# badger.net
KiCad netlist of a schematic drawn in EAGLE
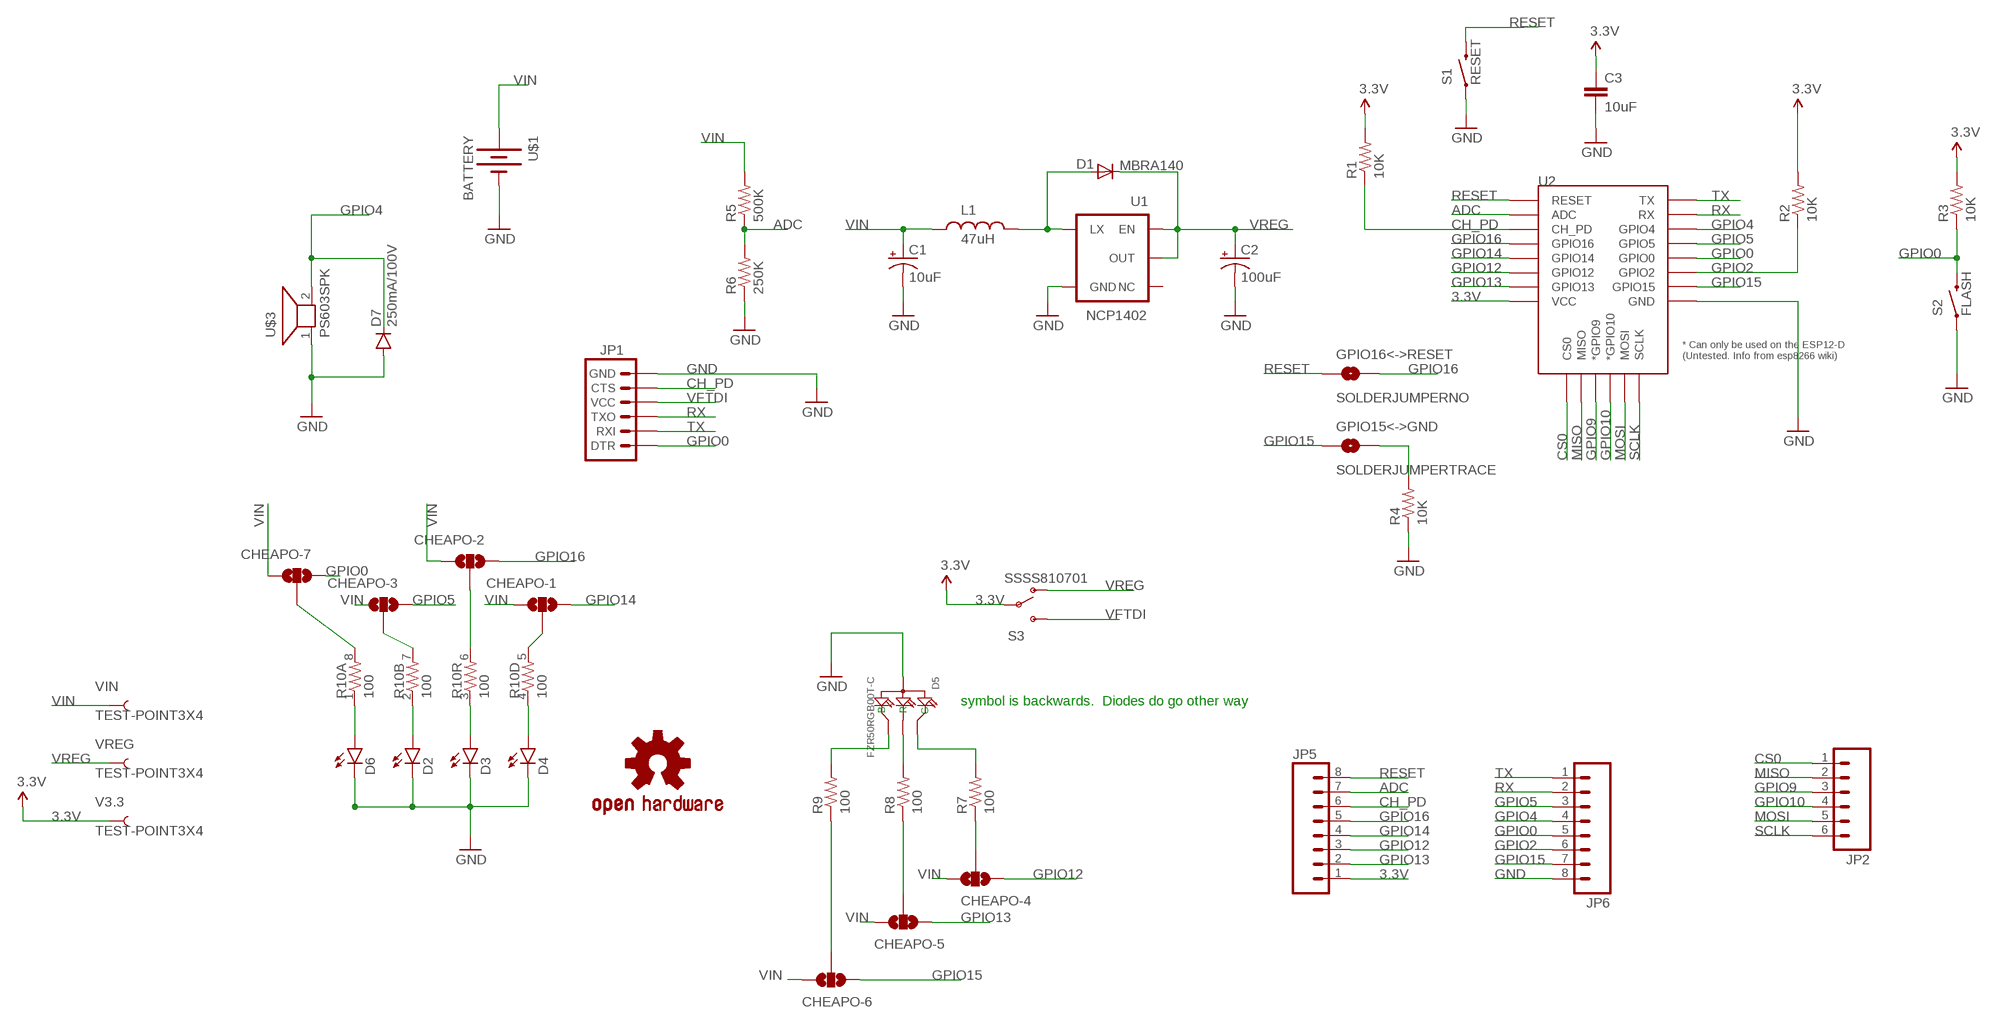
[diagram p0: schematic, sheet 1]

(export (version "E")
  (design (tool "Eeschema 10.0.6"))
  (components
    (comp (ref "C1")
      (value "10uF")
      (footprint "eagle-import:EIA3216")
      (libsource (lib "eagle-import") (part "CAP_POL1206"))
    )
    (comp (ref "C2")
      (value "100uF")
      (footprint "eagle-import:EIA3528")
      (libsource (lib "eagle-import") (part "CAP_POL3528"))
    )
    (comp (ref "C3")
      (value "10uF")
      (footprint "eagle-import:0603-CAP")
      (libsource (lib "eagle-import") (part "10UF-6.3V-20%(0603)"))
    )
    (comp (ref "CHEAPO-1")
      (value "SOLDERJUMPER_2WAYT")
      (footprint "eagle-import:SJ_2")
      (libsource (lib "eagle-import") (part "SOLDERJUMPER_2WAYT"))
    )
    (comp (ref "CHEAPO-2")
      (value "SOLDERJUMPER_2WAYT")
      (footprint "eagle-import:SJ_2")
      (libsource (lib "eagle-import") (part "SOLDERJUMPER_2WAYT"))
    )
    (comp (ref "CHEAPO-3")
      (value "SOLDERJUMPER_2WAYT")
      (footprint "eagle-import:SJ_2")
      (libsource (lib "eagle-import") (part "SOLDERJUMPER_2WAYT"))
    )
    (comp (ref "CHEAPO-4")
      (value "SOLDERJUMPER_2WAYT")
      (footprint "eagle-import:SJ_2")
      (libsource (lib "eagle-import") (part "SOLDERJUMPER_2WAYT"))
    )
    (comp (ref "CHEAPO-5")
      (value "SOLDERJUMPER_2WAYT")
      (footprint "eagle-import:SJ_2")
      (libsource (lib "eagle-import") (part "SOLDERJUMPER_2WAYT"))
    )
    (comp (ref "CHEAPO-6")
      (value "SOLDERJUMPER_2WAYT")
      (footprint "eagle-import:SJ_2")
      (libsource (lib "eagle-import") (part "SOLDERJUMPER_2WAYT"))
    )
    (comp (ref "CHEAPO-7")
      (value "SOLDERJUMPER_2WAYT")
      (footprint "eagle-import:SJ_2")
      (libsource (lib "eagle-import") (part "SOLDERJUMPER_2WAYT"))
    )
    (comp (ref "D1")
      (value "MBRA140")
      (footprint "eagle-import:SMA-DIODE")
      (libsource (lib "eagle-import") (part "DIODESMA"))
    )
    (comp (ref "D2")
      (value "LED-3MM-NO_SILK")
      (footprint "eagle-import:LED3MM-NS")
      (libsource (lib "eagle-import") (part "LED-3MM-NO_SILK"))
    )
    (comp (ref "D3")
      (value "LED-3MM-NO_SILK")
      (footprint "eagle-import:LED3MM-NS")
      (libsource (lib "eagle-import") (part "LED-3MM-NO_SILK"))
    )
    (comp (ref "D4")
      (value "LED-3MM-NO_SILK")
      (footprint "eagle-import:LED3MM-NS")
      (libsource (lib "eagle-import") (part "LED-3MM-NO_SILK"))
    )
    (comp (ref "D5")
      (value "FZR50RGB00T-C")
      (footprint "eagle-import:LED4-1.3-D5.0MM")
      (libsource (lib "eagle-import") (part "DIP-LED-RGB-COMMON-ANODE(4P-D5MM)"))
    )
    (comp (ref "D6")
      (value "LED-3MM-NO_SILK")
      (footprint "eagle-import:LED3MM-NS")
      (libsource (lib "eagle-import") (part "LED-3MM-NO_SILK"))
    )
    (comp (ref "D7")
      (value "250mA/100V")
      (footprint "eagle-import:SOD-323")
      (libsource (lib "eagle-import") (part "DIODEBAS16"))
    )
    (comp (ref "GPIO15<->GND")
      (value "SOLDERJUMPERTRACE")
      (footprint "eagle-import:SJ_2S-TRACE")
      (libsource (lib "eagle-import") (part "SOLDERJUMPERTRACE"))
    )
    (comp (ref "GPIO16<->RESET")
      (value "SOLDERJUMPERNO")
      (footprint "eagle-import:SJ_2S-NO")
      (libsource (lib "eagle-import") (part "SOLDERJUMPERNO"))
    )
    (comp (ref "JP1")
      (value "ARDUINO_SERIAL_PROGRAMLOCK")
      (footprint "eagle-import:1X06_LOCK")
      (libsource (lib "eagle-import") (part "ARDUINO_SERIAL_PROGRAMLOCK"))
    )
    (comp (ref "JP2")
      (value "M06LOCK")
      (footprint "eagle-import:1X06_LOCK")
      (libsource (lib "eagle-import") (part "M06LOCK"))
    )
    (comp (ref "JP5")
      (value "M08LOCK")
      (footprint "eagle-import:1X08_LOCK")
      (libsource (lib "eagle-import") (part "M08LOCK"))
    )
    (comp (ref "JP6")
      (value "M08LOCK")
      (footprint "eagle-import:1X08_LOCK")
      (libsource (lib "eagle-import") (part "M08LOCK"))
    )
    (comp (ref "L1")
      (value "47uH")
      (footprint "eagle-import:CR54")
      (libsource (lib "eagle-import") (part "INDUCTORCR54"))
    )
    (comp (ref "LOGO1")
      (value "OSHW-LOGOL-COPPER")
      (footprint "eagle-import:OSHW-LOGO-L_COPPER")
      (libsource (lib "eagle-import") (part "OSHW-LOGOL-COPPER"))
    )
    (comp (ref "R1")
      (value "10K")
      (footprint "eagle-import:0603-RES")
      (libsource (lib "eagle-import") (part "10KOHM-1/10W-1%(0603)0603"))
    )
    (comp (ref "R2")
      (value "10K")
      (footprint "eagle-import:0603-RES")
      (libsource (lib "eagle-import") (part "10KOHM-1/10W-1%(0603)0603"))
    )
    (comp (ref "R3")
      (value "10K")
      (footprint "eagle-import:0603-RES")
      (libsource (lib "eagle-import") (part "10KOHM-1/10W-1%(0603)0603"))
    )
    (comp (ref "R4")
      (value "10K")
      (footprint "eagle-import:0603-RES")
      (libsource (lib "eagle-import") (part "10KOHM-1/10W-1%(0603)0603"))
    )
    (comp (ref "R5")
      (value "500K")
      (footprint "eagle-import:0603-RES")
      (libsource (lib "eagle-import") (part "RESISTOR0603"))
    )
    (comp (ref "R6")
      (value "250K")
      (footprint "eagle-import:0603-RES")
      (libsource (lib "eagle-import") (part "RESISTOR0603"))
    )
    (comp (ref "R7")
      (value "100")
      (footprint "eagle-import:1206")
      (libsource (lib "eagle-import") (part "RESISTOR1206"))
    )
    (comp (ref "R8")
      (value "100")
      (footprint "eagle-import:1206")
      (libsource (lib "eagle-import") (part "RESISTOR1206"))
    )
    (comp (ref "R9")
      (value "100")
      (footprint "eagle-import:1206")
      (libsource (lib "eagle-import") (part "RESISTOR1206"))
    )
    (comp (ref "R10")
      (value "100")
      (footprint "eagle-import:0603-ARV")
      (libsource (lib "eagle-import") (part "RESISTOR-ARRAY0603-ARV"))
    )
    (comp (ref "S1")
      (value "RESET")
      (footprint "eagle-import:TACTILE-SWITCH-SMD")
      (libsource (lib "eagle-import") (part "SWITCH-MOMENTARY-2SMD"))
    )
    (comp (ref "S2")
      (value "FLASH")
      (footprint "eagle-import:TACTILE-SWITCH-SMD")
      (libsource (lib "eagle-import") (part "SWITCH-MOMENTARY-2SMD"))
    )
    (comp (ref "S3")
      (value "SSSS810701")
      (footprint "eagle-import:SSSS8")
      (libsource (lib "eagle-import") (part "SSSS810701"))
    )
    (comp (ref "U$1")
      (value "BATTERY")
      (footprint "eagle-import:HOLDER")
      (libsource (lib "eagle-import") (part "BATTERY"))
    )
    (comp (ref "U$3")
      (value "PS603SPK")
      (footprint "eagle-import:PS603")
      (libsource (lib "eagle-import") (part "PS603SPK"))
    )
    (comp (ref "U1")
      (value "NCP1402")
      (footprint "eagle-import:SOT23-5")
      (libsource (lib "eagle-import") (part "V_REG_NCP1400SOT23-5"))
    )
    (comp (ref "U2")
      (value "ESP12ESMD")
      (footprint "eagle-import:ESP12E-SMD")
      (libsource (lib "eagle-import") (part "ESP12ESMD"))
    )
    (comp (ref "V3.3")
      (value "TEST-POINT3X4")
      (footprint "eagle-import:PAD.03X.04")
      (libsource (lib "eagle-import") (part "TEST-POINT3X4"))
    )
    (comp (ref "VIN")
      (value "TEST-POINT3X4")
      (footprint "eagle-import:PAD.03X.04")
      (libsource (lib "eagle-import") (part "TEST-POINT3X4"))
    )
    (comp (ref "VREG")
      (value "TEST-POINT3X4")
      (footprint "eagle-import:PAD.03X.04")
      (libsource (lib "eagle-import") (part "TEST-POINT3X4"))
    )
  )
  (nets
    (net (code "1") (name "/ADC") (class "Default")
      (node (ref "JP5") (pin "7") (pinfunction "7_7") (pintype "passive"))
      (node (ref "R5") (pin "1") (pinfunction "1_1") (pintype "passive"))
      (node (ref "R6") (pin "2") (pinfunction "2_2") (pintype "passive"))
      (node (ref "U2") (pin "ADC") (pinfunction "ADC_ADC") (pintype "bidirectional"))
    )
    (net (code "2") (name "/CH_PD") (class "Default")
      (node (ref "JP1") (pin "5") (pinfunction "CTS_5") (pintype "passive"))
      (node (ref "JP5") (pin "6") (pinfunction "6_6") (pintype "passive"))
      (node (ref "R1") (pin "1") (pinfunction "1_1") (pintype "passive"))
      (node (ref "U2") (pin "CH_PD") (pinfunction "CH_PD_CH_PD") (pintype "bidirectional"))
    )
    (net (code "3") (name "/CS0") (class "Default")
      (node (ref "JP2") (pin "1") (pinfunction "1_1") (pintype "passive"))
      (node (ref "U2") (pin "CS0") (pinfunction "CS0_CS0") (pintype "bidirectional"))
    )
    (net (code "4") (name "/GPIO0") (class "Default")
      (node (ref "CHEAPO-7") (pin "3") (pinfunction "3_3") (pintype "passive"))
      (node (ref "JP1") (pin "1") (pinfunction "DTR_1") (pintype "passive"))
      (node (ref "JP6") (pin "5") (pinfunction "5_5") (pintype "passive"))
      (node (ref "R3") (pin "1") (pinfunction "1_1") (pintype "passive"))
      (node (ref "S2") (pin "3") (pinfunction "2_3") (pintype "passive"))
      (node (ref "U2") (pin "GPIO0") (pinfunction "GPIO0_GPIO0") (pintype "bidirectional"))
    )
    (net (code "5") (name "/GPIO2") (class "Default")
      (node (ref "JP6") (pin "6") (pinfunction "6_6") (pintype "passive"))
      (node (ref "R2") (pin "1") (pinfunction "1_1") (pintype "passive"))
      (node (ref "U2") (pin "GPIO2") (pinfunction "GPIO2_GPIO2") (pintype "bidirectional"))
    )
    (net (code "6") (name "/GPIO4") (class "Default")
      (node (ref "D7") (pin "C") (pinfunction "C_C") (pintype "passive"))
      (node (ref "JP6") (pin "4") (pinfunction "4_4") (pintype "passive"))
      (node (ref "U$3") (pin "2") (pinfunction "2_2") (pintype "passive"))
      (node (ref "U2") (pin "GPIO4") (pinfunction "GPIO4_GPIO4") (pintype "bidirectional"))
    )
    (net (code "7") (name "/GPIO5") (class "Default")
      (node (ref "CHEAPO-3") (pin "3") (pinfunction "3_3") (pintype "passive"))
      (node (ref "JP6") (pin "3") (pinfunction "3_3") (pintype "passive"))
      (node (ref "U2") (pin "GPIO5") (pinfunction "GPIO5_GPIO5") (pintype "bidirectional"))
    )
    (net (code "8") (name "/GPIO9") (class "Default")
      (node (ref "JP2") (pin "3") (pinfunction "3_3") (pintype "passive"))
      (node (ref "U2") (pin "GPIO9") (pinfunction "*GPIO9_GPIO9") (pintype "bidirectional"))
    )
    (net (code "9") (name "/GPIO10") (class "Default")
      (node (ref "JP2") (pin "4") (pinfunction "4_4") (pintype "passive"))
      (node (ref "U2") (pin "GPIO10") (pinfunction "*GPIO10_GPIO10") (pintype "bidirectional"))
    )
    (net (code "10") (name "/GPIO12") (class "Default")
      (node (ref "CHEAPO-4") (pin "1") (pinfunction "1_1") (pintype "passive"))
      (node (ref "JP5") (pin "3") (pinfunction "3_3") (pintype "passive"))
      (node (ref "U2") (pin "GPIO12") (pinfunction "GPIO12_GPIO12") (pintype "bidirectional"))
    )
    (net (code "11") (name "/GPIO13") (class "Default")
      (node (ref "CHEAPO-5") (pin "1") (pinfunction "1_1") (pintype "passive"))
      (node (ref "JP5") (pin "2") (pinfunction "2_2") (pintype "passive"))
      (node (ref "U2") (pin "GPIO13") (pinfunction "GPIO13_GPIO13") (pintype "bidirectional"))
    )
    (net (code "12") (name "/GPIO14") (class "Default")
      (node (ref "CHEAPO-1") (pin "3") (pinfunction "3_3") (pintype "passive"))
      (node (ref "JP5") (pin "4") (pinfunction "4_4") (pintype "passive"))
      (node (ref "U2") (pin "GPIO14") (pinfunction "GPIO14_GPIO14") (pintype "bidirectional"))
    )
    (net (code "13") (name "/GPIO15") (class "Default")
      (node (ref "CHEAPO-6") (pin "1") (pinfunction "1_1") (pintype "passive"))
      (node (ref "GPIO15<->GND") (pin "1") (pinfunction "1_1") (pintype "passive"))
      (node (ref "JP6") (pin "7") (pinfunction "7_7") (pintype "passive"))
      (node (ref "U2") (pin "GPIO15") (pinfunction "GPIO15_GPIO15") (pintype "bidirectional"))
    )
    (net (code "14") (name "/GPIO16") (class "Default")
      (node (ref "CHEAPO-2") (pin "3") (pinfunction "3_3") (pintype "passive"))
      (node (ref "GPIO16<->RESET") (pin "2") (pinfunction "2_2") (pintype "passive"))
      (node (ref "JP5") (pin "5") (pinfunction "5_5") (pintype "passive"))
      (node (ref "U2") (pin "GPIO16") (pinfunction "GPIO16_GPIO16") (pintype "bidirectional"))
    )
    (net (code "15") (name "/MISO") (class "Default")
      (node (ref "JP2") (pin "2") (pinfunction "2_2") (pintype "passive"))
      (node (ref "U2") (pin "MISO") (pinfunction "MISO_MISO") (pintype "bidirectional"))
    )
    (net (code "16") (name "/MOSI") (class "Default")
      (node (ref "JP2") (pin "5") (pinfunction "5_5") (pintype "passive"))
      (node (ref "U2") (pin "MOSI") (pinfunction "MOSI_MOSI") (pintype "bidirectional"))
    )
    (net (code "17") (name "/RESET") (class "Default")
      (node (ref "GPIO16<->RESET") (pin "1") (pinfunction "1_1") (pintype "passive"))
      (node (ref "JP5") (pin "8") (pinfunction "8_8") (pintype "passive"))
      (node (ref "S1") (pin "3") (pinfunction "2_3") (pintype "passive"))
      (node (ref "U2") (pin "RESET") (pinfunction "RESET_RESET") (pintype "bidirectional"))
    )
    (net (code "18") (name "/RX") (class "Default")
      (node (ref "JP1") (pin "3") (pinfunction "TXO_3") (pintype "passive"))
      (node (ref "JP6") (pin "2") (pinfunction "2_2") (pintype "passive"))
      (node (ref "U2") (pin "RXD0") (pinfunction "RX_RXD0") (pintype "bidirectional"))
    )
    (net (code "19") (name "/SCLK") (class "Default")
      (node (ref "JP2") (pin "6") (pinfunction "6_6") (pintype "passive"))
      (node (ref "U2") (pin "SCLK") (pinfunction "SCLK_SCLK") (pintype "bidirectional"))
    )
    (net (code "20") (name "/TX") (class "Default")
      (node (ref "JP1") (pin "2") (pinfunction "RXI_2") (pintype "passive"))
      (node (ref "JP6") (pin "1") (pinfunction "1_1") (pintype "passive"))
      (node (ref "U2") (pin "TXD0") (pinfunction "TX_TXD0") (pintype "bidirectional"))
    )
    (net (code "21") (name "/VFTDI") (class "Default")
      (node (ref "JP1") (pin "4") (pinfunction "VCC_4") (pintype "passive"))
      (node (ref "S3") (pin "P$1") (pinfunction "S_P$1") (pintype "passive"))
    )
    (net (code "22") (name "/VIN") (class "Default")
      (node (ref "C1") (pin "A") (pinfunction "+_A") (pintype "passive"))
      (node (ref "CHEAPO-1") (pin "1") (pinfunction "1_1") (pintype "passive"))
      (node (ref "CHEAPO-2") (pin "1") (pinfunction "1_1") (pintype "passive"))
      (node (ref "CHEAPO-3") (pin "1") (pinfunction "1_1") (pintype "passive"))
      (node (ref "CHEAPO-4") (pin "3") (pinfunction "3_3") (pintype "passive"))
      (node (ref "CHEAPO-5") (pin "3") (pinfunction "3_3") (pintype "passive"))
      (node (ref "CHEAPO-6") (pin "3") (pinfunction "3_3") (pintype "passive"))
      (node (ref "CHEAPO-7") (pin "1") (pinfunction "1_1") (pintype "passive"))
      (node (ref "L1") (pin "P$1") (pinfunction "1_P$1") (pintype "passive"))
      (node (ref "R5") (pin "2") (pinfunction "2_2") (pintype "passive"))
      (node (ref "U$1") (pin "P$1") (pinfunction "+_P$1") (pintype "power_in"))
      (node (ref "VIN") (pin "P$1") (pinfunction "1_P$1") (pintype "bidirectional"))
    )
    (net (code "23") (name "/VREG") (class "Default")
      (node (ref "C2") (pin "A") (pinfunction "+_A") (pintype "passive"))
      (node (ref "D1") (pin "C") (pinfunction "C_C") (pintype "passive"))
      (node (ref "S3") (pin "P$3") (pinfunction "O_P$3") (pintype "passive"))
      (node (ref "U1") (pin "1") (pinfunction "EN_1") (pintype "input"))
      (node (ref "U1") (pin "2") (pinfunction "OUT_2") (pintype "passive"))
      (node (ref "VREG") (pin "P$1") (pinfunction "1_P$1") (pintype "bidirectional"))
    )
    (net (code "24") (name "3.3V") (class "Default")
      (node (ref "C3") (pin "1") (pinfunction "1_1") (pintype "passive"))
      (node (ref "JP5") (pin "1") (pinfunction "1_1") (pintype "passive"))
      (node (ref "R1") (pin "2") (pinfunction "2_2") (pintype "passive"))
      (node (ref "R2") (pin "2") (pinfunction "2_2") (pintype "passive"))
      (node (ref "R3") (pin "2") (pinfunction "2_2") (pintype "passive"))
      (node (ref "S3") (pin "P$2") (pinfunction "P_P$2") (pintype "passive"))
      (node (ref "U2") (pin "VCC") (pinfunction "VCC_VCC") (pintype "bidirectional"))
      (node (ref "V3.3") (pin "P$1") (pinfunction "1_P$1") (pintype "bidirectional"))
    )
    (net (code "25") (name "GND") (class "Default")
      (node (ref "C1") (pin "C") (pinfunction "-_C") (pintype "passive"))
      (node (ref "C2") (pin "C") (pinfunction "-_C") (pintype "passive"))
      (node (ref "C3") (pin "2") (pinfunction "2_2") (pintype "passive"))
      (node (ref "D2") (pin "K") (pinfunction "C_K") (pintype "passive"))
      (node (ref "D3") (pin "K") (pinfunction "C_K") (pintype "passive"))
      (node (ref "D4") (pin "K") (pinfunction "C_K") (pintype "passive"))
      (node (ref "D5") (pin "C") (pinfunction "+_C") (pintype "bidirectional"))
      (node (ref "D6") (pin "K") (pinfunction "C_K") (pintype "passive"))
      (node (ref "D7") (pin "A") (pinfunction "A_A") (pintype "passive"))
      (node (ref "JP1") (pin "6") (pinfunction "GND_6") (pintype "passive"))
      (node (ref "JP6") (pin "8") (pinfunction "8_8") (pintype "passive"))
      (node (ref "R4") (pin "1") (pinfunction "1_1") (pintype "passive"))
      (node (ref "R6") (pin "1") (pinfunction "1_1") (pintype "passive"))
      (node (ref "S1") (pin "1") (pinfunction "1_1") (pintype "passive"))
      (node (ref "S2") (pin "1") (pinfunction "1_1") (pintype "passive"))
      (node (ref "U$1") (pin "P$2") (pinfunction "-_P$2") (pintype "power_in"))
      (node (ref "U$3") (pin "1") (pinfunction "1_1") (pintype "passive"))
      (node (ref "U1") (pin "4") (pinfunction "GND_4") (pintype "input"))
      (node (ref "U2") (pin "GND") (pinfunction "GND_GND") (pintype "bidirectional"))
    )
    (net (code "26") (name "Net-(CHEAPO-4-Pad2)") (class "Default")
      (node (ref "CHEAPO-4") (pin "2") (pinfunction "2_2") (pintype "passive"))
      (node (ref "R7") (pin "1") (pinfunction "1_1") (pintype "passive"))
    )
    (net (code "27") (name "Net-(CHEAPO-5-Pad2)") (class "Default")
      (node (ref "CHEAPO-5") (pin "2") (pinfunction "2_2") (pintype "passive"))
      (node (ref "R8") (pin "1") (pinfunction "1_1") (pintype "passive"))
    )
    (net (code "28") (name "Net-(CHEAPO-6-Pad2)") (class "Default")
      (node (ref "CHEAPO-6") (pin "2") (pinfunction "2_2") (pintype "passive"))
      (node (ref "R9") (pin "1") (pinfunction "1_1") (pintype "passive"))
    )
    (net (code "29") (name "Net-(D5-PadB)") (class "Default")
      (node (ref "D5") (pin "B") (pinfunction "B_B") (pintype "bidirectional"))
      (node (ref "R9") (pin "2") (pinfunction "2_2") (pintype "passive"))
    )
    (net (code "30") (name "Net-(D5-PadG)") (class "Default")
      (node (ref "D5") (pin "G") (pinfunction "G_G") (pintype "bidirectional"))
      (node (ref "R7") (pin "2") (pinfunction "2_2") (pintype "passive"))
    )
    (net (code "31") (name "Net-(D5-PadR)") (class "Default")
      (node (ref "D5") (pin "R") (pinfunction "R_R") (pintype "bidirectional"))
      (node (ref "R8") (pin "2") (pinfunction "2_2") (pintype "passive"))
    )
    (net (code "32") (name "Net-(D6-PadA)") (class "Default")
      (node (ref "D6") (pin "A") (pinfunction "A_A") (pintype "passive"))
      (node (ref "R10") (pin "1") (pinfunction "1_1") (pintype "passive"))
    )
    (net (code "33") (name "Net-(GPIO15<->GND-Pad2)") (class "Default")
      (node (ref "GPIO15<->GND") (pin "2") (pinfunction "2_2") (pintype "passive"))
      (node (ref "R4") (pin "2") (pinfunction "2_2") (pintype "passive"))
    )
    (net (code "34") (name "Net-(L1-2)") (class "Default")
      (node (ref "D1") (pin "A") (pinfunction "A_A") (pintype "passive"))
      (node (ref "L1") (pin "P$2") (pinfunction "2_P$2") (pintype "passive"))
      (node (ref "U1") (pin "5") (pinfunction "LX_5") (pintype "input"))
    )
    (net (code "35") (name "Net-(R10A-2)") (class "Default")
      (node (ref "CHEAPO-7") (pin "2") (pinfunction "2_2") (pintype "passive"))
      (node (ref "R10") (pin "8") (pinfunction "2_8") (pintype "passive"))
    )
    (net (code "36") (name "Net-(R10B-1)") (class "Default")
      (node (ref "D2") (pin "A") (pinfunction "A_A") (pintype "passive"))
      (node (ref "R10") (pin "2") (pinfunction "1_2") (pintype "passive"))
    )
    (net (code "37") (name "Net-(R10B-2)") (class "Default")
      (node (ref "CHEAPO-3") (pin "2") (pinfunction "2_2") (pintype "passive"))
      (node (ref "R10") (pin "7") (pinfunction "2_7") (pintype "passive"))
    )
    (net (code "38") (name "Net-(R10C-1)") (class "Default")
      (node (ref "D4") (pin "A") (pinfunction "A_A") (pintype "passive"))
      (node (ref "R10") (pin "4") (pinfunction "1_4") (pintype "passive"))
    )
    (net (code "39") (name "Net-(R10C-2)") (class "Default")
      (node (ref "CHEAPO-1") (pin "2") (pinfunction "2_2") (pintype "passive"))
      (node (ref "R10") (pin "5") (pinfunction "2_5") (pintype "passive"))
    )
    (net (code "40") (name "Net-(R10D-1)") (class "Default")
      (node (ref "D3") (pin "A") (pinfunction "A_A") (pintype "passive"))
      (node (ref "R10") (pin "3") (pinfunction "1_3") (pintype "passive"))
    )
    (net (code "41") (name "Net-(R10D-2)") (class "Default")
      (node (ref "CHEAPO-2") (pin "2") (pinfunction "2_2") (pintype "passive"))
      (node (ref "R10") (pin "6") (pinfunction "2_6") (pintype "passive"))
    )
    (net (code "42") (name "unconnected-(U1-NC-Pad3)") (class "Default")
      (node (ref "U1") (pin "3") (pinfunction "NC_3") (pintype "input"))
    )
  )
)
